# neonred-schematic-2026-10-05.net
KiCad netlist of a schematic drawn in EasyEDA
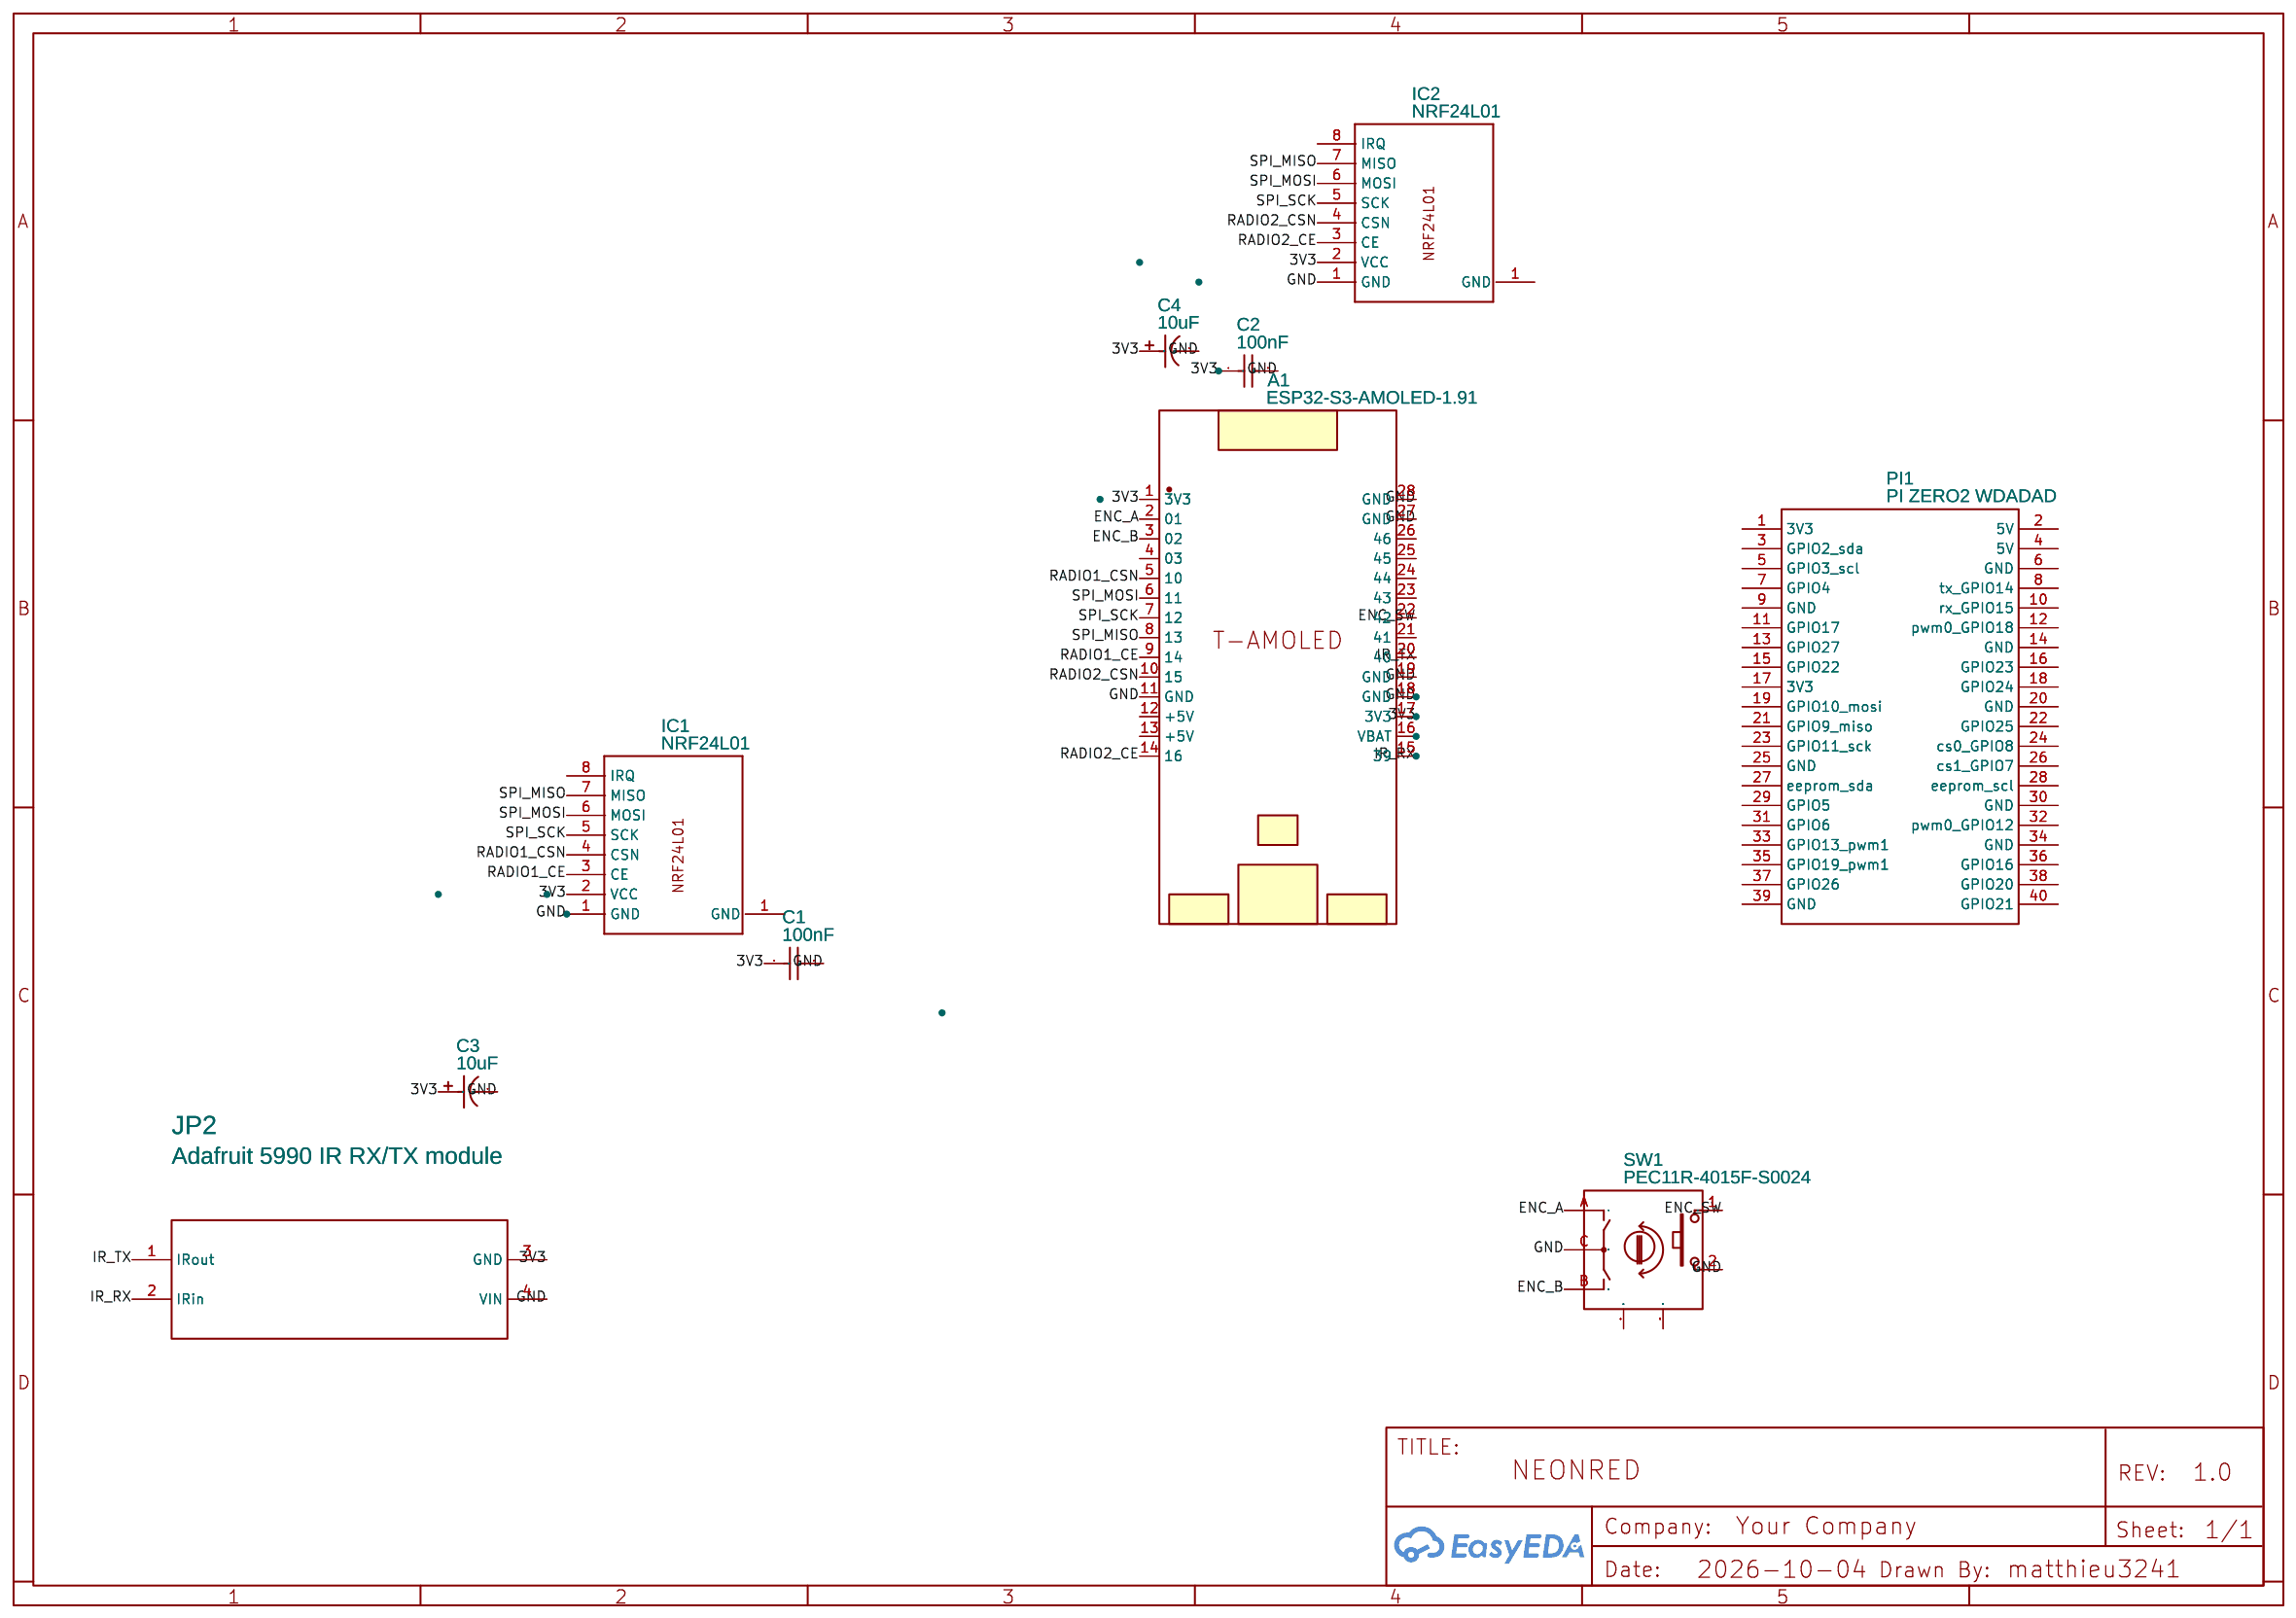
[diagram p0: schematic sheet]

(export (version "E")
  (design (tool "Eeschema 10.0.6"))
  (components
    (comp (ref "A1")
      (value "ESP32-S3-AMOLED-1.91")
      (fields (field (name "Manufacturer Part") "T-Display S3 AMOLED") (field (name "Manufacturer") "Lilygo"))
      (libsource (lib "") (part "ESP32-S3-AMOLED-1.91"))
    )
    (comp (ref "C1")
      (value "100nF")
      (fields (field (name "Manufacturer Part") "0.1UF(104) +-20% 63v"))
      (libsource (lib "") (part "100nF"))
    )
    (comp (ref "C2")
      (value "100nF")
      (fields (field (name "Manufacturer Part") "0.1UF(104) +-20% 63v"))
      (libsource (lib "") (part "100nF"))
    )
    (comp (ref "C3") (value "10uF") (libsource (lib "") (part "Capacitor 10uF TH")))
    (comp (ref "C4") (value "10uF") (libsource (lib "") (part "Capacitor 10uF TH")))
    (comp (ref "IC1") (value "NRF24L01") (libsource (lib "") (part "NRF24L01")))
    (comp (ref "IC2") (value "NRF24L01") (libsource (lib "") (part "NRF24L01")))
    (comp (ref "JP2") (value "Adafruit 5990 IR RX/TX module") (libsource (lib "") (part "M04")))
    (comp (ref "PI1") (value "PI ZERO2 WDADAD") (libsource (lib "") (part "PI ZERO2 WDADAD")))
    (comp (ref "SW1")
      (value "PEC11R-4015F-S0024")
      (fields (field (name "Manufacturer") "BOURNS"))
      (libsource (lib "") (part "PEC11R-4015F-S0024"))
    )
  )
  (nets
    (net (code "1") (name "/3V3") (class "Default")
      (node (ref "A1") (pin "1") (pinfunction "3V3_1") (pintype "unspecified"))
      (node (ref "A1") (pin "17") (pinfunction "3V3_17") (pintype "unspecified"))
      (node (ref "C1") (pin "1") (pinfunction "1_1") (pintype "input"))
      (node (ref "C2") (pin "1") (pinfunction "1_1") (pintype "input"))
      (node (ref "C3") (pin "1") (pinfunction "1_1") (pintype "input"))
      (node (ref "C4") (pin "1") (pinfunction "1_1") (pintype "input"))
      (node (ref "IC1") (pin "2") (pinfunction "VCC_2") (pintype "bidirectional"))
      (node (ref "IC2") (pin "2") (pinfunction "VCC_2") (pintype "bidirectional"))
      (node (ref "JP2") (pin "3") (pinfunction "GND_3") (pintype "unspecified"))
    )
    (net (code "2") (name "/ENC_A") (class "Default")
      (node (ref "A1") (pin "2") (pinfunction "01_2") (pintype "unspecified"))
      (node (ref "SW1") (pin "A") (pinfunction "A_A") (pintype "unspecified"))
    )
    (net (code "3") (name "/ENC_B") (class "Default")
      (node (ref "A1") (pin "3") (pinfunction "02_3") (pintype "unspecified"))
      (node (ref "SW1") (pin "B") (pinfunction "B_B") (pintype "unspecified"))
    )
    (net (code "4") (name "/ENC_SW") (class "Default")
      (node (ref "A1") (pin "22") (pinfunction "42_22") (pintype "unspecified"))
      (node (ref "SW1") (pin "1") (pinfunction "1_1") (pintype "unspecified"))
    )
    (net (code "5") (name "/GND") (class "Default")
      (node (ref "A1") (pin "11") (pinfunction "GND_11") (pintype "unspecified"))
      (node (ref "A1") (pin "18") (pinfunction "GND_18") (pintype "unspecified"))
      (node (ref "A1") (pin "19") (pinfunction "GND_19") (pintype "unspecified"))
      (node (ref "A1") (pin "27") (pinfunction "GND_27") (pintype "unspecified"))
      (node (ref "A1") (pin "28") (pinfunction "GND_28") (pintype "unspecified"))
      (node (ref "C1") (pin "2") (pinfunction "2_2") (pintype "input"))
      (node (ref "C2") (pin "2") (pinfunction "2_2") (pintype "input"))
      (node (ref "C3") (pin "2") (pinfunction "2_2") (pintype "input"))
      (node (ref "C4") (pin "2") (pinfunction "2_2") (pintype "input"))
      (node (ref "IC1") (pin "1") (pinfunction "GND_1") (pintype "bidirectional"))
      (node (ref "IC2") (pin "1") (pinfunction "GND_1") (pintype "bidirectional"))
      (node (ref "JP2") (pin "4") (pinfunction "VIN_4") (pintype "unspecified"))
      (node (ref "SW1") (pin "2") (pinfunction "2_2") (pintype "unspecified"))
      (node (ref "SW1") (pin "C") (pinfunction "C_C") (pintype "unspecified"))
    )
    (net (code "6") (name "/IR_RX") (class "Default")
      (node (ref "A1") (pin "15") (pinfunction "39_15") (pintype "unspecified"))
      (node (ref "JP2") (pin "2") (pinfunction "IRin_2") (pintype "unspecified"))
    )
    (net (code "7") (name "/IR_TX") (class "Default")
      (node (ref "A1") (pin "20") (pinfunction "40_20") (pintype "unspecified"))
      (node (ref "JP2") (pin "1") (pinfunction "IRout_1") (pintype "unspecified"))
    )
    (net (code "8") (name "/RADIO1_CE") (class "Default")
      (node (ref "A1") (pin "9") (pinfunction "14_9") (pintype "unspecified"))
      (node (ref "IC1") (pin "3") (pinfunction "CE_3") (pintype "bidirectional"))
    )
    (net (code "9") (name "/RADIO1_CSN") (class "Default")
      (node (ref "A1") (pin "5") (pinfunction "10_5") (pintype "unspecified"))
      (node (ref "IC1") (pin "4") (pinfunction "CSN_4") (pintype "bidirectional"))
    )
    (net (code "10") (name "/RADIO2_CE") (class "Default")
      (node (ref "A1") (pin "14") (pinfunction "16_14") (pintype "unspecified"))
      (node (ref "IC2") (pin "3") (pinfunction "CE_3") (pintype "bidirectional"))
    )
    (net (code "11") (name "/RADIO2_CSN") (class "Default")
      (node (ref "A1") (pin "10") (pinfunction "15_10") (pintype "unspecified"))
      (node (ref "IC2") (pin "4") (pinfunction "CSN_4") (pintype "bidirectional"))
    )
    (net (code "12") (name "/SPI_MISO") (class "Default")
      (node (ref "A1") (pin "8") (pinfunction "13_8") (pintype "unspecified"))
      (node (ref "IC1") (pin "7") (pinfunction "MISO_7") (pintype "bidirectional"))
      (node (ref "IC2") (pin "7") (pinfunction "MISO_7") (pintype "bidirectional"))
    )
    (net (code "13") (name "/SPI_MOSI") (class "Default")
      (node (ref "A1") (pin "6") (pinfunction "11_6") (pintype "unspecified"))
      (node (ref "IC1") (pin "6") (pinfunction "MOSI_6") (pintype "bidirectional"))
      (node (ref "IC2") (pin "6") (pinfunction "MOSI_6") (pintype "bidirectional"))
    )
    (net (code "14") (name "/SPI_SCK") (class "Default")
      (node (ref "A1") (pin "7") (pinfunction "12_7") (pintype "unspecified"))
      (node (ref "IC1") (pin "5") (pinfunction "SCK_5") (pintype "bidirectional"))
      (node (ref "IC2") (pin "5") (pinfunction "SCK_5") (pintype "bidirectional"))
    )
    (net (code "15") (name "unconnected-(A1-+5V-Pad12)") (class "Default")
      (node (ref "A1") (pin "12") (pinfunction "+5V_12") (pintype "unspecified"))
    )
    (net (code "16") (name "unconnected-(A1-+5V-Pad13)") (class "Default")
      (node (ref "A1") (pin "13") (pinfunction "+5V_13") (pintype "unspecified"))
    )
    (net (code "17") (name "unconnected-(A1-03-Pad4)") (class "Default")
      (node (ref "A1") (pin "4") (pinfunction "03_4") (pintype "unspecified"))
    )
    (net (code "18") (name "unconnected-(A1-41-Pad21)") (class "Default")
      (node (ref "A1") (pin "21") (pinfunction "41_21") (pintype "unspecified"))
    )
    (net (code "19") (name "unconnected-(A1-43-Pad23)") (class "Default")
      (node (ref "A1") (pin "23") (pinfunction "43_23") (pintype "unspecified"))
    )
    (net (code "20") (name "unconnected-(A1-44-Pad24)") (class "Default")
      (node (ref "A1") (pin "24") (pinfunction "44_24") (pintype "unspecified"))
    )
    (net (code "21") (name "unconnected-(A1-45-Pad25)") (class "Default")
      (node (ref "A1") (pin "25") (pinfunction "45_25") (pintype "unspecified"))
    )
    (net (code "22") (name "unconnected-(A1-46-Pad26)") (class "Default")
      (node (ref "A1") (pin "26") (pinfunction "46_26") (pintype "unspecified"))
    )
    (net (code "23") (name "unconnected-(A1-VBAT-Pad16)") (class "Default")
      (node (ref "A1") (pin "16") (pinfunction "VBAT_16") (pintype "unspecified"))
    )
    (net (code "24") (name "unconnected-(IC1-GND-Pad1)") (class "Default")
      (node (ref "IC1") (pin "1") (pinfunction "GND_1") (pintype "bidirectional"))
    )
    (net (code "25") (name "unconnected-(IC1-IRQ-Pad8)") (class "Default")
      (node (ref "IC1") (pin "8") (pinfunction "IRQ_8") (pintype "bidirectional"))
    )
    (net (code "26") (name "unconnected-(IC2-GND-Pad1)") (class "Default")
      (node (ref "IC2") (pin "1") (pinfunction "GND_1") (pintype "bidirectional"))
    )
    (net (code "27") (name "unconnected-(IC2-IRQ-Pad8)") (class "Default")
      (node (ref "IC2") (pin "8") (pinfunction "IRQ_8") (pintype "bidirectional"))
    )
    (net (code "28") (name "unconnected-(PI1-3V3-Pad1)") (class "Default")
      (node (ref "PI1") (pin "1") (pinfunction "3V3_1") (pintype "unspecified"))
    )
    (net (code "29") (name "unconnected-(PI1-3V3-Pad17)") (class "Default")
      (node (ref "PI1") (pin "17") (pinfunction "3V3_17") (pintype "unspecified"))
    )
    (net (code "30") (name "unconnected-(PI1-5V-Pad2)") (class "Default")
      (node (ref "PI1") (pin "2") (pinfunction "5V_2") (pintype "unspecified"))
    )
    (net (code "31") (name "unconnected-(PI1-5V-Pad4)") (class "Default")
      (node (ref "PI1") (pin "4") (pinfunction "5V_4") (pintype "unspecified"))
    )
    (net (code "32") (name "unconnected-(PI1-GND-Pad6)") (class "Default")
      (node (ref "PI1") (pin "6") (pinfunction "GND_6") (pintype "unspecified"))
    )
    (net (code "33") (name "unconnected-(PI1-GND-Pad9)") (class "Default")
      (node (ref "PI1") (pin "9") (pinfunction "GND_9") (pintype "unspecified"))
    )
    (net (code "34") (name "unconnected-(PI1-GND-Pad14)") (class "Default")
      (node (ref "PI1") (pin "14") (pinfunction "GND_14") (pintype "unspecified"))
    )
    (net (code "35") (name "unconnected-(PI1-GND-Pad20)") (class "Default")
      (node (ref "PI1") (pin "20") (pinfunction "GND_20") (pintype "unspecified"))
    )
    (net (code "36") (name "unconnected-(PI1-GND-Pad25)") (class "Default")
      (node (ref "PI1") (pin "25") (pinfunction "GND_25") (pintype "unspecified"))
    )
    (net (code "37") (name "unconnected-(PI1-GND-Pad30)") (class "Default")
      (node (ref "PI1") (pin "30") (pinfunction "GND_30") (pintype "unspecified"))
    )
    (net (code "38") (name "unconnected-(PI1-GND-Pad34)") (class "Default")
      (node (ref "PI1") (pin "34") (pinfunction "GND_34") (pintype "unspecified"))
    )
    (net (code "39") (name "unconnected-(PI1-GND-Pad39)") (class "Default")
      (node (ref "PI1") (pin "39") (pinfunction "GND_39") (pintype "unspecified"))
    )
    (net (code "40") (name "unconnected-(PI1-GPIO2_sda-Pad3)") (class "Default")
      (node (ref "PI1") (pin "3") (pinfunction "GPIO2_sda_3") (pintype "unspecified"))
    )
    (net (code "41") (name "unconnected-(PI1-GPIO3_scl-Pad5)") (class "Default")
      (node (ref "PI1") (pin "5") (pinfunction "GPIO3_scl_5") (pintype "unspecified"))
    )
    (net (code "42") (name "unconnected-(PI1-GPIO4-Pad7)") (class "Default")
      (node (ref "PI1") (pin "7") (pinfunction "GPIO4_7") (pintype "unspecified"))
    )
    (net (code "43") (name "unconnected-(PI1-GPIO5-Pad29)") (class "Default")
      (node (ref "PI1") (pin "29") (pinfunction "GPIO5_29") (pintype "unspecified"))
    )
    (net (code "44") (name "unconnected-(PI1-GPIO6-Pad31)") (class "Default")
      (node (ref "PI1") (pin "31") (pinfunction "GPIO6_31") (pintype "unspecified"))
    )
    (net (code "45") (name "unconnected-(PI1-GPIO9_miso-Pad21)") (class "Default")
      (node (ref "PI1") (pin "21") (pinfunction "GPIO9_miso_21") (pintype "unspecified"))
    )
    (net (code "46") (name "unconnected-(PI1-GPIO10_mosi-Pad19)") (class "Default")
      (node (ref "PI1") (pin "19") (pinfunction "GPIO10_mosi_19") (pintype "unspecified"))
    )
    (net (code "47") (name "unconnected-(PI1-GPIO11_sck-Pad23)") (class "Default")
      (node (ref "PI1") (pin "23") (pinfunction "GPIO11_sck_23") (pintype "unspecified"))
    )
    (net (code "48") (name "unconnected-(PI1-GPIO13_pwm1-Pad33)") (class "Default")
      (node (ref "PI1") (pin "33") (pinfunction "GPIO13_pwm1_33") (pintype "unspecified"))
    )
    (net (code "49") (name "unconnected-(PI1-GPIO16-Pad36)") (class "Default")
      (node (ref "PI1") (pin "36") (pinfunction "GPIO16_36") (pintype "unspecified"))
    )
    (net (code "50") (name "unconnected-(PI1-GPIO17-Pad11)") (class "Default")
      (node (ref "PI1") (pin "11") (pinfunction "GPIO17_11") (pintype "unspecified"))
    )
    (net (code "51") (name "unconnected-(PI1-GPIO19_pwm1-Pad35)") (class "Default")
      (node (ref "PI1") (pin "35") (pinfunction "GPIO19_pwm1_35") (pintype "unspecified"))
    )
    (net (code "52") (name "unconnected-(PI1-GPIO20-Pad38)") (class "Default")
      (node (ref "PI1") (pin "38") (pinfunction "GPIO20_38") (pintype "unspecified"))
    )
    (net (code "53") (name "unconnected-(PI1-GPIO21-Pad40)") (class "Default")
      (node (ref "PI1") (pin "40") (pinfunction "GPIO21_40") (pintype "unspecified"))
    )
    (net (code "54") (name "unconnected-(PI1-GPIO22-Pad15)") (class "Default")
      (node (ref "PI1") (pin "15") (pinfunction "GPIO22_15") (pintype "unspecified"))
    )
    (net (code "55") (name "unconnected-(PI1-GPIO23-Pad16)") (class "Default")
      (node (ref "PI1") (pin "16") (pinfunction "GPIO23_16") (pintype "unspecified"))
    )
    (net (code "56") (name "unconnected-(PI1-GPIO24-Pad18)") (class "Default")
      (node (ref "PI1") (pin "18") (pinfunction "GPIO24_18") (pintype "unspecified"))
    )
    (net (code "57") (name "unconnected-(PI1-GPIO25-Pad22)") (class "Default")
      (node (ref "PI1") (pin "22") (pinfunction "GPIO25_22") (pintype "unspecified"))
    )
    (net (code "58") (name "unconnected-(PI1-GPIO26-Pad37)") (class "Default")
      (node (ref "PI1") (pin "37") (pinfunction "GPIO26_37") (pintype "unspecified"))
    )
    (net (code "59") (name "unconnected-(PI1-GPIO27-Pad13)") (class "Default")
      (node (ref "PI1") (pin "13") (pinfunction "GPIO27_13") (pintype "unspecified"))
    )
    (net (code "60") (name "unconnected-(PI1-cs0_GPIO8-Pad24)") (class "Default")
      (node (ref "PI1") (pin "24") (pinfunction "cs0_GPIO8_24") (pintype "unspecified"))
    )
    (net (code "61") (name "unconnected-(PI1-cs1_GPIO7-Pad26)") (class "Default")
      (node (ref "PI1") (pin "26") (pinfunction "cs1_GPIO7_26") (pintype "unspecified"))
    )
    (net (code "62") (name "unconnected-(PI1-eeprom_scl-Pad28)") (class "Default")
      (node (ref "PI1") (pin "28") (pinfunction "eeprom_scl_28") (pintype "unspecified"))
    )
    (net (code "63") (name "unconnected-(PI1-eeprom_sda-Pad27)") (class "Default")
      (node (ref "PI1") (pin "27") (pinfunction "eeprom_sda_27") (pintype "unspecified"))
    )
    (net (code "64") (name "unconnected-(PI1-pwm0_GPIO12-Pad32)") (class "Default")
      (node (ref "PI1") (pin "32") (pinfunction "pwm0_GPIO12_32") (pintype "unspecified"))
    )
    (net (code "65") (name "unconnected-(PI1-pwm0_GPIO18-Pad12)") (class "Default")
      (node (ref "PI1") (pin "12") (pinfunction "pwm0_GPIO18_12") (pintype "unspecified"))
    )
    (net (code "66") (name "unconnected-(PI1-rx_GPIO15-Pad10)") (class "Default")
      (node (ref "PI1") (pin "10") (pinfunction "rx_GPIO15_10") (pintype "unspecified"))
    )
    (net (code "67") (name "unconnected-(PI1-tx_GPIO14-Pad8)") (class "Default")
      (node (ref "PI1") (pin "8") (pinfunction "tx_GPIO14_8") (pintype "unspecified"))
    )
    (net (code "68") (name "unconnected-(SW1-PadMT1)") (class "Default")
      (node (ref "SW1") (pin "MT1") (pinfunction "MT1_MT1") (pintype "unspecified"))
    )
    (net (code "69") (name "unconnected-(SW1-PadMT2)") (class "Default")
      (node (ref "SW1") (pin "MT2") (pinfunction "MT2_MT2") (pintype "unspecified"))
    )
  )
)
